# EInkRainGaugePCB.net
KiCad netlist of a schematic drawn in Altium Designer
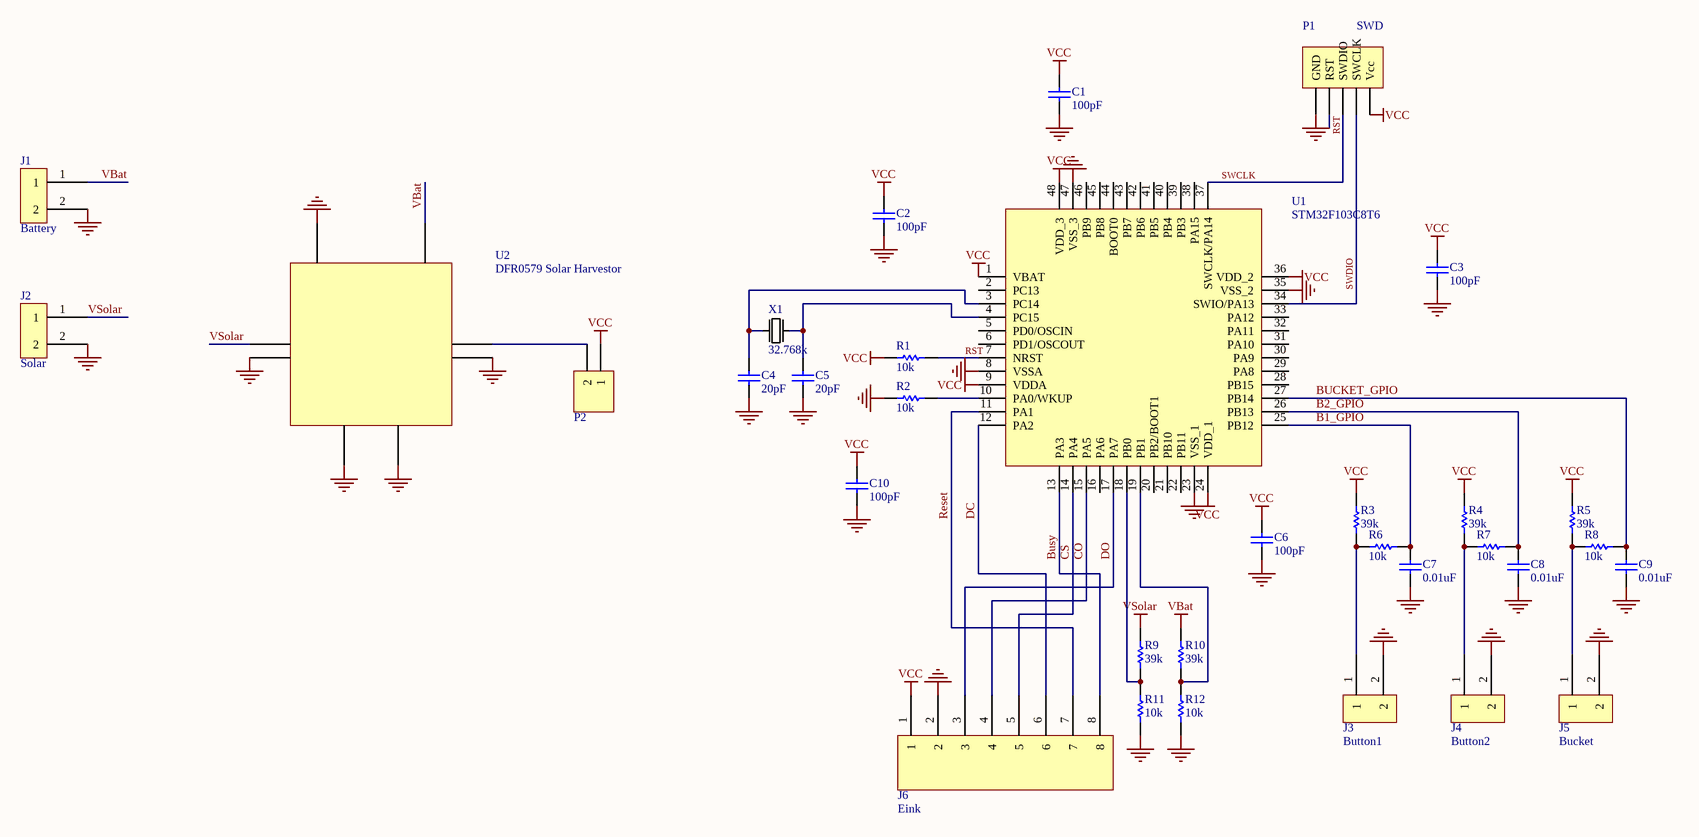
[diagram p0: EInkRainGaugePCB.SchDoc]

(export (version "E")
  (design (tool "Eeschema 10.0.6"))
  (components
    (comp (ref "C1")
      (value "100pF")
      (footprint "Cap SMD 0805A")
      (description "Capacitor")
      (fields (field (name "Comment") "Cap") (field (name "PUBLISHER") "Altium Limited"))
      (libsource (lib "Custom") (part "Cap"))
    )
    (comp (ref "C2")
      (value "100pF")
      (footprint "Cap SMD 0805A")
      (description "Capacitor")
      (fields (field (name "Comment") "Cap") (field (name "PUBLISHER") "Altium Limited"))
      (libsource (lib "Custom") (part "Cap"))
    )
    (comp (ref "C3")
      (value "100pF")
      (footprint "Cap SMD 0805A")
      (description "Capacitor")
      (fields (field (name "Comment") "Cap") (field (name "PUBLISHER") "Altium Limited"))
      (libsource (lib "Custom") (part "Cap"))
    )
    (comp (ref "C4")
      (value "20pF")
      (footprint "Cap SMD 0805A")
      (description "Capacitor")
      (fields (field (name "Comment") "Cap") (field (name "PUBLISHER") "Altium Limited"))
      (libsource (lib "Custom") (part "Cap"))
    )
    (comp (ref "C5")
      (value "20pF")
      (footprint "Cap SMD 0805A")
      (description "Capacitor")
      (fields (field (name "Comment") "Cap") (field (name "PUBLISHER") "Altium Limited"))
      (libsource (lib "Custom") (part "Cap"))
    )
    (comp (ref "C6")
      (value "100pF")
      (footprint "Cap SMD 0805A")
      (description "Capacitor")
      (fields (field (name "Comment") "Cap") (field (name "PUBLISHER") "Altium Limited"))
      (libsource (lib "Custom") (part "Cap"))
    )
    (comp (ref "C7")
      (value "0.01uF")
      (footprint "Cap SMD 0805A")
      (description "Capacitor")
      (fields (field (name "Comment") "Cap") (field (name "PUBLISHER") "Altium Limited"))
      (libsource (lib "Custom") (part "Cap"))
    )
    (comp (ref "C8")
      (value "0.01uF")
      (footprint "Cap SMD 0805A")
      (description "Capacitor")
      (fields (field (name "Comment") "Cap") (field (name "PUBLISHER") "Altium Limited"))
      (libsource (lib "Custom") (part "Cap"))
    )
    (comp (ref "C9")
      (value "0.01uF")
      (footprint "Cap SMD 0805A")
      (description "Capacitor")
      (fields (field (name "Comment") "Cap") (field (name "PUBLISHER") "Altium Limited"))
      (libsource (lib "Custom") (part "Cap"))
    )
    (comp (ref "C10")
      (value "100pF")
      (footprint "Cap SMD 0805A")
      (description "Capacitor")
      (fields (field (name "Comment") "Cap") (field (name "PUBLISHER") "Altium Limited"))
      (libsource (lib "Custom") (part "Cap"))
    )
    (comp (ref "J1") (value "Battery") (footprint "JST PH 2") (libsource (lib "") (part "SIP2 CONNECTOR_1")))
    (comp (ref "J2") (value "Solar") (footprint "JST PH 2") (libsource (lib "") (part "SIP2 CONNECTOR_1")))
    (comp (ref "J3")
      (value "Button1")
      (footprint "JST PH 2")
      (libsource (lib "Custom") (part "SIP2 CONNECTOR"))
    )
    (comp (ref "J4")
      (value "Button2")
      (footprint "JST PH 2")
      (libsource (lib "Custom") (part "SIP2 CONNECTOR"))
    )
    (comp (ref "J5")
      (value "Bucket")
      (footprint "JST PH 2")
      (libsource (lib "Custom") (part "SIP2 CONNECTOR"))
    )
    (comp (ref "J6") (value "Eink") (footprint "JST PH 8") (libsource (lib "Custom") (part "SIP8 CONNECTOR")))
    (comp (ref "P1")
      (value "SWD")
      (footprint "HDR1X5")
      (description "Header, 5-Pin")
      (fields (field (name "PUBLISHER") "Altium Limited"))
      (libsource (lib "Miscellaneous Connectors") (part "Header 5"))
    )
    (comp (ref "P2")
      (value "Power Monitor")
      (footprint "HDR1X2")
      (description "Header, 2-Pin")
      (fields (field (name "PUBLISHER") "Altium Limited"))
      (libsource (lib "Miscellaneous Connectors") (part "Header 2"))
    )
    (comp (ref "R1")
      (value "10k")
      (footprint "Res SMD 0805A")
      (fields (field (name "Comment") "Res1"))
      (libsource (lib "Custom") (part "Resistor"))
    )
    (comp (ref "R2")
      (value "10k")
      (footprint "Res SMD 0805A")
      (fields (field (name "Comment") "Res1"))
      (libsource (lib "Custom") (part "Resistor"))
    )
    (comp (ref "R3")
      (value "39k")
      (footprint "Res SMD 0805A")
      (fields (field (name "Comment") "Res1"))
      (libsource (lib "Custom") (part "Resistor"))
    )
    (comp (ref "R4")
      (value "39k")
      (footprint "Res SMD 0805A")
      (fields (field (name "Comment") "Res1"))
      (libsource (lib "Custom") (part "Resistor"))
    )
    (comp (ref "R5")
      (value "39k")
      (footprint "Res SMD 0805A")
      (fields (field (name "Comment") "Res1"))
      (libsource (lib "Custom") (part "Resistor"))
    )
    (comp (ref "R6")
      (value "10k")
      (footprint "Res SMD 0805A")
      (fields (field (name "Comment") "Res1"))
      (libsource (lib "Custom") (part "Resistor"))
    )
    (comp (ref "R7")
      (value "10k")
      (footprint "Res SMD 0805A")
      (fields (field (name "Comment") "Res1"))
      (libsource (lib "Custom") (part "Resistor"))
    )
    (comp (ref "R8")
      (value "10k")
      (footprint "Res SMD 0805A")
      (fields (field (name "Comment") "Res1"))
      (libsource (lib "Custom") (part "Resistor"))
    )
    (comp (ref "R9")
      (value "39k")
      (footprint "Res SMD 0805A")
      (fields (field (name "Comment") "Res1"))
      (libsource (lib "Custom") (part "Resistor"))
    )
    (comp (ref "R10")
      (value "39k")
      (footprint "Res SMD 0805A")
      (fields (field (name "Comment") "Res1"))
      (libsource (lib "Custom") (part "Resistor"))
    )
    (comp (ref "R11")
      (value "10k")
      (footprint "Res SMD 0805A")
      (fields (field (name "Comment") "Res1"))
      (libsource (lib "Custom") (part "Resistor"))
    )
    (comp (ref "R12")
      (value "10k")
      (footprint "Res SMD 0805A")
      (fields (field (name "Comment") "Res1"))
      (libsource (lib "Custom") (part "Resistor"))
    )
    (comp (ref "U1")
      (value "STM32F103C8T6")
      (footprint "LQFP48")
      (libsource (lib "Custom") (part "STM32F103C8T6"))
    )
    (comp (ref "U2")
      (value "DFR0579 Solar Harvestor")
      (footprint "DFR0579 Solar Harvester")
      (libsource (lib "Custom") (part "DFR0579 Solar Harvestor"))
    )
    (comp (ref "X1")
      (value "32.768k")
      (footprint "Crystal - Cylinder")
      (fields (field (name "Comment") "XTAL"))
      (libsource (lib "Custom") (part "Crystal"))
    )
  )
  (nets
    (net (code "1") (name "/B1_GPIO") (class "Default")
      (node (ref "C7") (pin "2") (pinfunction "2_2") (pintype "passive"))
      (node (ref "R6") (pin "2") (pinfunction "2_2") (pintype "passive"))
      (node (ref "U1") (pin "25") (pinfunction "PB12_25") (pintype "passive"))
    )
    (net (code "2") (name "/B2_GPIO") (class "Default")
      (node (ref "C8") (pin "2") (pinfunction "2_2") (pintype "passive"))
      (node (ref "R7") (pin "2") (pinfunction "2_2") (pintype "passive"))
      (node (ref "U1") (pin "26") (pinfunction "PB13_26") (pintype "passive"))
    )
    (net (code "3") (name "/BUCKET_GPIO") (class "Default")
      (node (ref "C9") (pin "2") (pinfunction "2_2") (pintype "passive"))
      (node (ref "R8") (pin "2") (pinfunction "2_2") (pintype "passive"))
      (node (ref "U1") (pin "27") (pinfunction "PB14_27") (pintype "passive"))
    )
    (net (code "4") (name "/Busy") (class "Default")
      (node (ref "J6") (pin "8") (pinfunction "8_8") (pintype "passive"))
      (node (ref "U1") (pin "13") (pinfunction "PA3_13") (pintype "passive"))
    )
    (net (code "5") (name "/CO") (class "Default")
      (node (ref "J6") (pin "4") (pinfunction "4_4") (pintype "passive"))
      (node (ref "U1") (pin "15") (pinfunction "PA5_15") (pintype "passive"))
    )
    (net (code "6") (name "/CS") (class "Default")
      (node (ref "J6") (pin "5") (pinfunction "5_5") (pintype "passive"))
      (node (ref "U1") (pin "14") (pinfunction "PA4_14") (pintype "passive"))
    )
    (net (code "7") (name "/DC") (class "Default")
      (node (ref "J6") (pin "6") (pinfunction "6_6") (pintype "passive"))
      (node (ref "U1") (pin "12") (pinfunction "PA2_12") (pintype "passive"))
    )
    (net (code "8") (name "/DO") (class "Default")
      (node (ref "J6") (pin "3") (pinfunction "3_3") (pintype "passive"))
      (node (ref "U1") (pin "17") (pinfunction "PA7_17") (pintype "passive"))
    )
    (net (code "9") (name "/RST") (class "Default")
      (node (ref "P1") (pin "4") (pinfunction "RST_4") (pintype "passive"))
      (node (ref "R1") (pin "1") (pinfunction "1_1") (pintype "passive"))
      (node (ref "U1") (pin "7") (pinfunction "NRST_7") (pintype "passive"))
    )
    (net (code "10") (name "/Reset") (class "Default")
      (node (ref "J6") (pin "7") (pinfunction "7_7") (pintype "passive"))
      (node (ref "U1") (pin "11") (pinfunction "PA1_11") (pintype "passive"))
    )
    (net (code "11") (name "/SWCLK") (class "Default")
      (node (ref "P1") (pin "3") (pinfunction "SWDIO_3") (pintype "passive"))
      (node (ref "U1") (pin "37") (pinfunction "SWCLK/PA14_37") (pintype "passive"))
    )
    (net (code "12") (name "/SWDIO") (class "Default")
      (node (ref "P1") (pin "2") (pinfunction "SWCLK_2") (pintype "passive"))
      (node (ref "U1") (pin "34") (pinfunction "SWIO/PA13_34") (pintype "passive"))
    )
    (net (code "13") (name "GND") (class "Default")
      (node (ref "C1") (pin "1") (pinfunction "1_1") (pintype "passive"))
      (node (ref "C10") (pin "1") (pinfunction "1_1") (pintype "passive"))
      (node (ref "C2") (pin "1") (pinfunction "1_1") (pintype "passive"))
      (node (ref "C3") (pin "1") (pinfunction "1_1") (pintype "passive"))
      (node (ref "C4") (pin "1") (pinfunction "1_1") (pintype "passive"))
      (node (ref "C5") (pin "1") (pinfunction "1_1") (pintype "passive"))
      (node (ref "C6") (pin "1") (pinfunction "1_1") (pintype "passive"))
      (node (ref "C7") (pin "1") (pinfunction "1_1") (pintype "passive"))
      (node (ref "C8") (pin "1") (pinfunction "1_1") (pintype "passive"))
      (node (ref "C9") (pin "1") (pinfunction "1_1") (pintype "passive"))
      (node (ref "J1") (pin "2") (pinfunction "2_2") (pintype "passive"))
      (node (ref "J2") (pin "2") (pinfunction "2_2") (pintype "passive"))
      (node (ref "J3") (pin "2") (pinfunction "2_2") (pintype "passive"))
      (node (ref "J4") (pin "2") (pinfunction "2_2") (pintype "passive"))
      (node (ref "J5") (pin "2") (pinfunction "2_2") (pintype "passive"))
      (node (ref "J6") (pin "2") (pinfunction "2_2") (pintype "passive"))
      (node (ref "P1") (pin "5") (pinfunction "GND_5") (pintype "passive"))
      (node (ref "R11") (pin "2") (pinfunction "2_2") (pintype "passive"))
      (node (ref "R12") (pin "2") (pinfunction "2_2") (pintype "passive"))
      (node (ref "R2") (pin "2") (pinfunction "2_2") (pintype "passive"))
      (node (ref "U1") (pin "23") (pinfunction "VSS_1_23") (pintype "passive"))
      (node (ref "U1") (pin "35") (pinfunction "VSS_2_35") (pintype "passive"))
      (node (ref "U1") (pin "47") (pinfunction "VSS_3_47") (pintype "passive"))
      (node (ref "U1") (pin "8") (pinfunction "VSSA_8") (pintype "passive"))
      (node (ref "U2") (pin "2") (pinfunction "SolarIn_-_2") (pintype "passive"))
      (node (ref "U2") (pin "4") (pinfunction "Out_3v3_-_4") (pintype "passive"))
      (node (ref "U2") (pin "6") (pinfunction "BatIn-_6") (pintype "passive"))
      (node (ref "U2") (pin "7") (pinfunction "GND_7") (pintype "passive"))
      (node (ref "U2") (pin "8") (pinfunction "GND_8") (pintype "passive"))
    )
    (net (code "14") (name "Net-(J3-Pad1)") (class "Default")
      (node (ref "J3") (pin "1") (pinfunction "1_1") (pintype "passive"))
      (node (ref "R3") (pin "2") (pinfunction "2_2") (pintype "passive"))
      (node (ref "R6") (pin "1") (pinfunction "1_1") (pintype "passive"))
    )
    (net (code "15") (name "Net-(J4-Pad1)") (class "Default")
      (node (ref "J4") (pin "1") (pinfunction "1_1") (pintype "passive"))
      (node (ref "R4") (pin "2") (pinfunction "2_2") (pintype "passive"))
      (node (ref "R7") (pin "1") (pinfunction "1_1") (pintype "passive"))
    )
    (net (code "16") (name "Net-(J5-Pad1)") (class "Default")
      (node (ref "J5") (pin "1") (pinfunction "1_1") (pintype "passive"))
      (node (ref "R5") (pin "2") (pinfunction "2_2") (pintype "passive"))
      (node (ref "R8") (pin "1") (pinfunction "1_1") (pintype "passive"))
    )
    (net (code "17") (name "Net-(U1-PA0{slash}WKUP)") (class "Default")
      (node (ref "R2") (pin "1") (pinfunction "1_1") (pintype "passive"))
      (node (ref "U1") (pin "10") (pinfunction "PA0/WKUP_10") (pintype "passive"))
    )
    (net (code "18") (name "Net-(U1-PB0)") (class "Default")
      (node (ref "R11") (pin "1") (pinfunction "1_1") (pintype "passive"))
      (node (ref "R9") (pin "2") (pinfunction "2_2") (pintype "passive"))
      (node (ref "U1") (pin "18") (pinfunction "PB0_18") (pintype "passive"))
    )
    (net (code "19") (name "Net-(U1-PB1)") (class "Default")
      (node (ref "R10") (pin "2") (pinfunction "2_2") (pintype "passive"))
      (node (ref "R12") (pin "1") (pinfunction "1_1") (pintype "passive"))
      (node (ref "U1") (pin "19") (pinfunction "PB1_19") (pintype "passive"))
    )
    (net (code "20") (name "Net-(U1-PC14)") (class "Default")
      (node (ref "C4") (pin "2") (pinfunction "2_2") (pintype "passive"))
      (node (ref "U1") (pin "3") (pinfunction "PC14_3") (pintype "passive"))
      (node (ref "X1") (pin "2") (pintype "passive"))
    )
    (net (code "21") (name "Net-(U1-PC15)") (class "Default")
      (node (ref "C5") (pin "2") (pinfunction "2_2") (pintype "passive"))
      (node (ref "U1") (pin "4") (pinfunction "PC15_4") (pintype "passive"))
      (node (ref "X1") (pin "1") (pintype "passive"))
    )
    (net (code "22") (name "Net-(U2-Out_3v3_+)") (class "Default")
      (node (ref "P2") (pin "2") (pinfunction "2_2") (pintype "passive"))
      (node (ref "U2") (pin "3") (pinfunction "Out_3v3_+_3") (pintype "passive"))
    )
    (net (code "23") (name "VBat") (class "Default")
      (node (ref "J1") (pin "1") (pinfunction "1_1") (pintype "passive"))
      (node (ref "R10") (pin "1") (pinfunction "1_1") (pintype "passive"))
      (node (ref "U2") (pin "5") (pinfunction "BatIn+_5") (pintype "passive"))
    )
    (net (code "24") (name "VCC") (class "Default")
      (node (ref "C1") (pin "2") (pinfunction "2_2") (pintype "passive"))
      (node (ref "C10") (pin "2") (pinfunction "2_2") (pintype "passive"))
      (node (ref "C2") (pin "2") (pinfunction "2_2") (pintype "passive"))
      (node (ref "C3") (pin "2") (pinfunction "2_2") (pintype "passive"))
      (node (ref "C6") (pin "2") (pinfunction "2_2") (pintype "passive"))
      (node (ref "J6") (pin "1") (pinfunction "1_1") (pintype "passive"))
      (node (ref "P1") (pin "1") (pinfunction "Vcc_1") (pintype "passive"))
      (node (ref "P2") (pin "1") (pinfunction "1_1") (pintype "passive"))
      (node (ref "R1") (pin "2") (pinfunction "2_2") (pintype "passive"))
      (node (ref "R3") (pin "1") (pinfunction "1_1") (pintype "passive"))
      (node (ref "R4") (pin "1") (pinfunction "1_1") (pintype "passive"))
      (node (ref "R5") (pin "1") (pinfunction "1_1") (pintype "passive"))
      (node (ref "U1") (pin "1") (pinfunction "VBAT_1") (pintype "passive"))
      (node (ref "U1") (pin "24") (pinfunction "VDD_1_24") (pintype "passive"))
      (node (ref "U1") (pin "36") (pinfunction "VDD_2_36") (pintype "passive"))
      (node (ref "U1") (pin "48") (pinfunction "VDD_3_48") (pintype "passive"))
      (node (ref "U1") (pin "9") (pinfunction "VDDA_9") (pintype "passive"))
    )
    (net (code "25") (name "VSolar") (class "Default")
      (node (ref "J2") (pin "1") (pinfunction "1_1") (pintype "passive"))
      (node (ref "R9") (pin "1") (pinfunction "1_1") (pintype "passive"))
      (node (ref "U2") (pin "1") (pinfunction "SolarIn_+_1") (pintype "passive"))
    )
    (net (code "26") (name "unconnected-(U1-BOOT0-Pad44)") (class "Default")
      (node (ref "U1") (pin "44") (pinfunction "BOOT0_44") (pintype "passive"))
    )
    (net (code "27") (name "unconnected-(U1-PA6-Pad16)") (class "Default")
      (node (ref "U1") (pin "16") (pinfunction "PA6_16") (pintype "passive"))
    )
    (net (code "28") (name "unconnected-(U1-PA8-Pad29)") (class "Default")
      (node (ref "U1") (pin "29") (pinfunction "PA8_29") (pintype "passive"))
    )
    (net (code "29") (name "unconnected-(U1-PA9-Pad30)") (class "Default")
      (node (ref "U1") (pin "30") (pinfunction "PA9_30") (pintype "passive"))
    )
    (net (code "30") (name "unconnected-(U1-PA10-Pad31)") (class "Default")
      (node (ref "U1") (pin "31") (pinfunction "PA10_31") (pintype "passive"))
    )
    (net (code "31") (name "unconnected-(U1-PA11-Pad32)") (class "Default")
      (node (ref "U1") (pin "32") (pinfunction "PA11_32") (pintype "passive"))
    )
    (net (code "32") (name "unconnected-(U1-PA12-Pad33)") (class "Default")
      (node (ref "U1") (pin "33") (pinfunction "PA12_33") (pintype "passive"))
    )
    (net (code "33") (name "unconnected-(U1-PA15-Pad38)") (class "Default")
      (node (ref "U1") (pin "38") (pinfunction "PA15_38") (pintype "passive"))
    )
    (net (code "34") (name "unconnected-(U1-PB2{slash}BOOT1-Pad20)") (class "Default")
      (node (ref "U1") (pin "20") (pinfunction "PB2/BOOT1_20") (pintype "passive"))
    )
    (net (code "35") (name "unconnected-(U1-PB3-Pad39)") (class "Default")
      (node (ref "U1") (pin "39") (pinfunction "PB3_39") (pintype "passive"))
    )
    (net (code "36") (name "unconnected-(U1-PB4-Pad40)") (class "Default")
      (node (ref "U1") (pin "40") (pinfunction "PB4_40") (pintype "passive"))
    )
    (net (code "37") (name "unconnected-(U1-PB5-Pad41)") (class "Default")
      (node (ref "U1") (pin "41") (pinfunction "PB5_41") (pintype "passive"))
    )
    (net (code "38") (name "unconnected-(U1-PB6-Pad42)") (class "Default")
      (node (ref "U1") (pin "42") (pinfunction "PB6_42") (pintype "passive"))
    )
    (net (code "39") (name "unconnected-(U1-PB7-Pad43)") (class "Default")
      (node (ref "U1") (pin "43") (pinfunction "PB7_43") (pintype "passive"))
    )
    (net (code "40") (name "unconnected-(U1-PB8-Pad45)") (class "Default")
      (node (ref "U1") (pin "45") (pinfunction "PB8_45") (pintype "passive"))
    )
    (net (code "41") (name "unconnected-(U1-PB9-Pad46)") (class "Default")
      (node (ref "U1") (pin "46") (pinfunction "PB9_46") (pintype "passive"))
    )
    (net (code "42") (name "unconnected-(U1-PB10-Pad21)") (class "Default")
      (node (ref "U1") (pin "21") (pinfunction "PB10_21") (pintype "passive"))
    )
    (net (code "43") (name "unconnected-(U1-PB11-Pad22)") (class "Default")
      (node (ref "U1") (pin "22") (pinfunction "PB11_22") (pintype "passive"))
    )
    (net (code "44") (name "unconnected-(U1-PB15-Pad28)") (class "Default")
      (node (ref "U1") (pin "28") (pinfunction "PB15_28") (pintype "passive"))
    )
    (net (code "45") (name "unconnected-(U1-PC13-Pad2)") (class "Default")
      (node (ref "U1") (pin "2") (pinfunction "PC13_2") (pintype "passive"))
    )
    (net (code "46") (name "unconnected-(U1-PD0{slash}OSCIN-Pad5)") (class "Default")
      (node (ref "U1") (pin "5") (pinfunction "PD0/OSCIN_5") (pintype "passive"))
    )
    (net (code "47") (name "unconnected-(U1-PD1{slash}OSCOUT-Pad6)") (class "Default")
      (node (ref "U1") (pin "6") (pinfunction "PD1/OSCOUT_6") (pintype "passive"))
    )
  )
)
